# Load_Cell_Biasing.net
KiCad netlist of a schematic drawn in Altium Designer
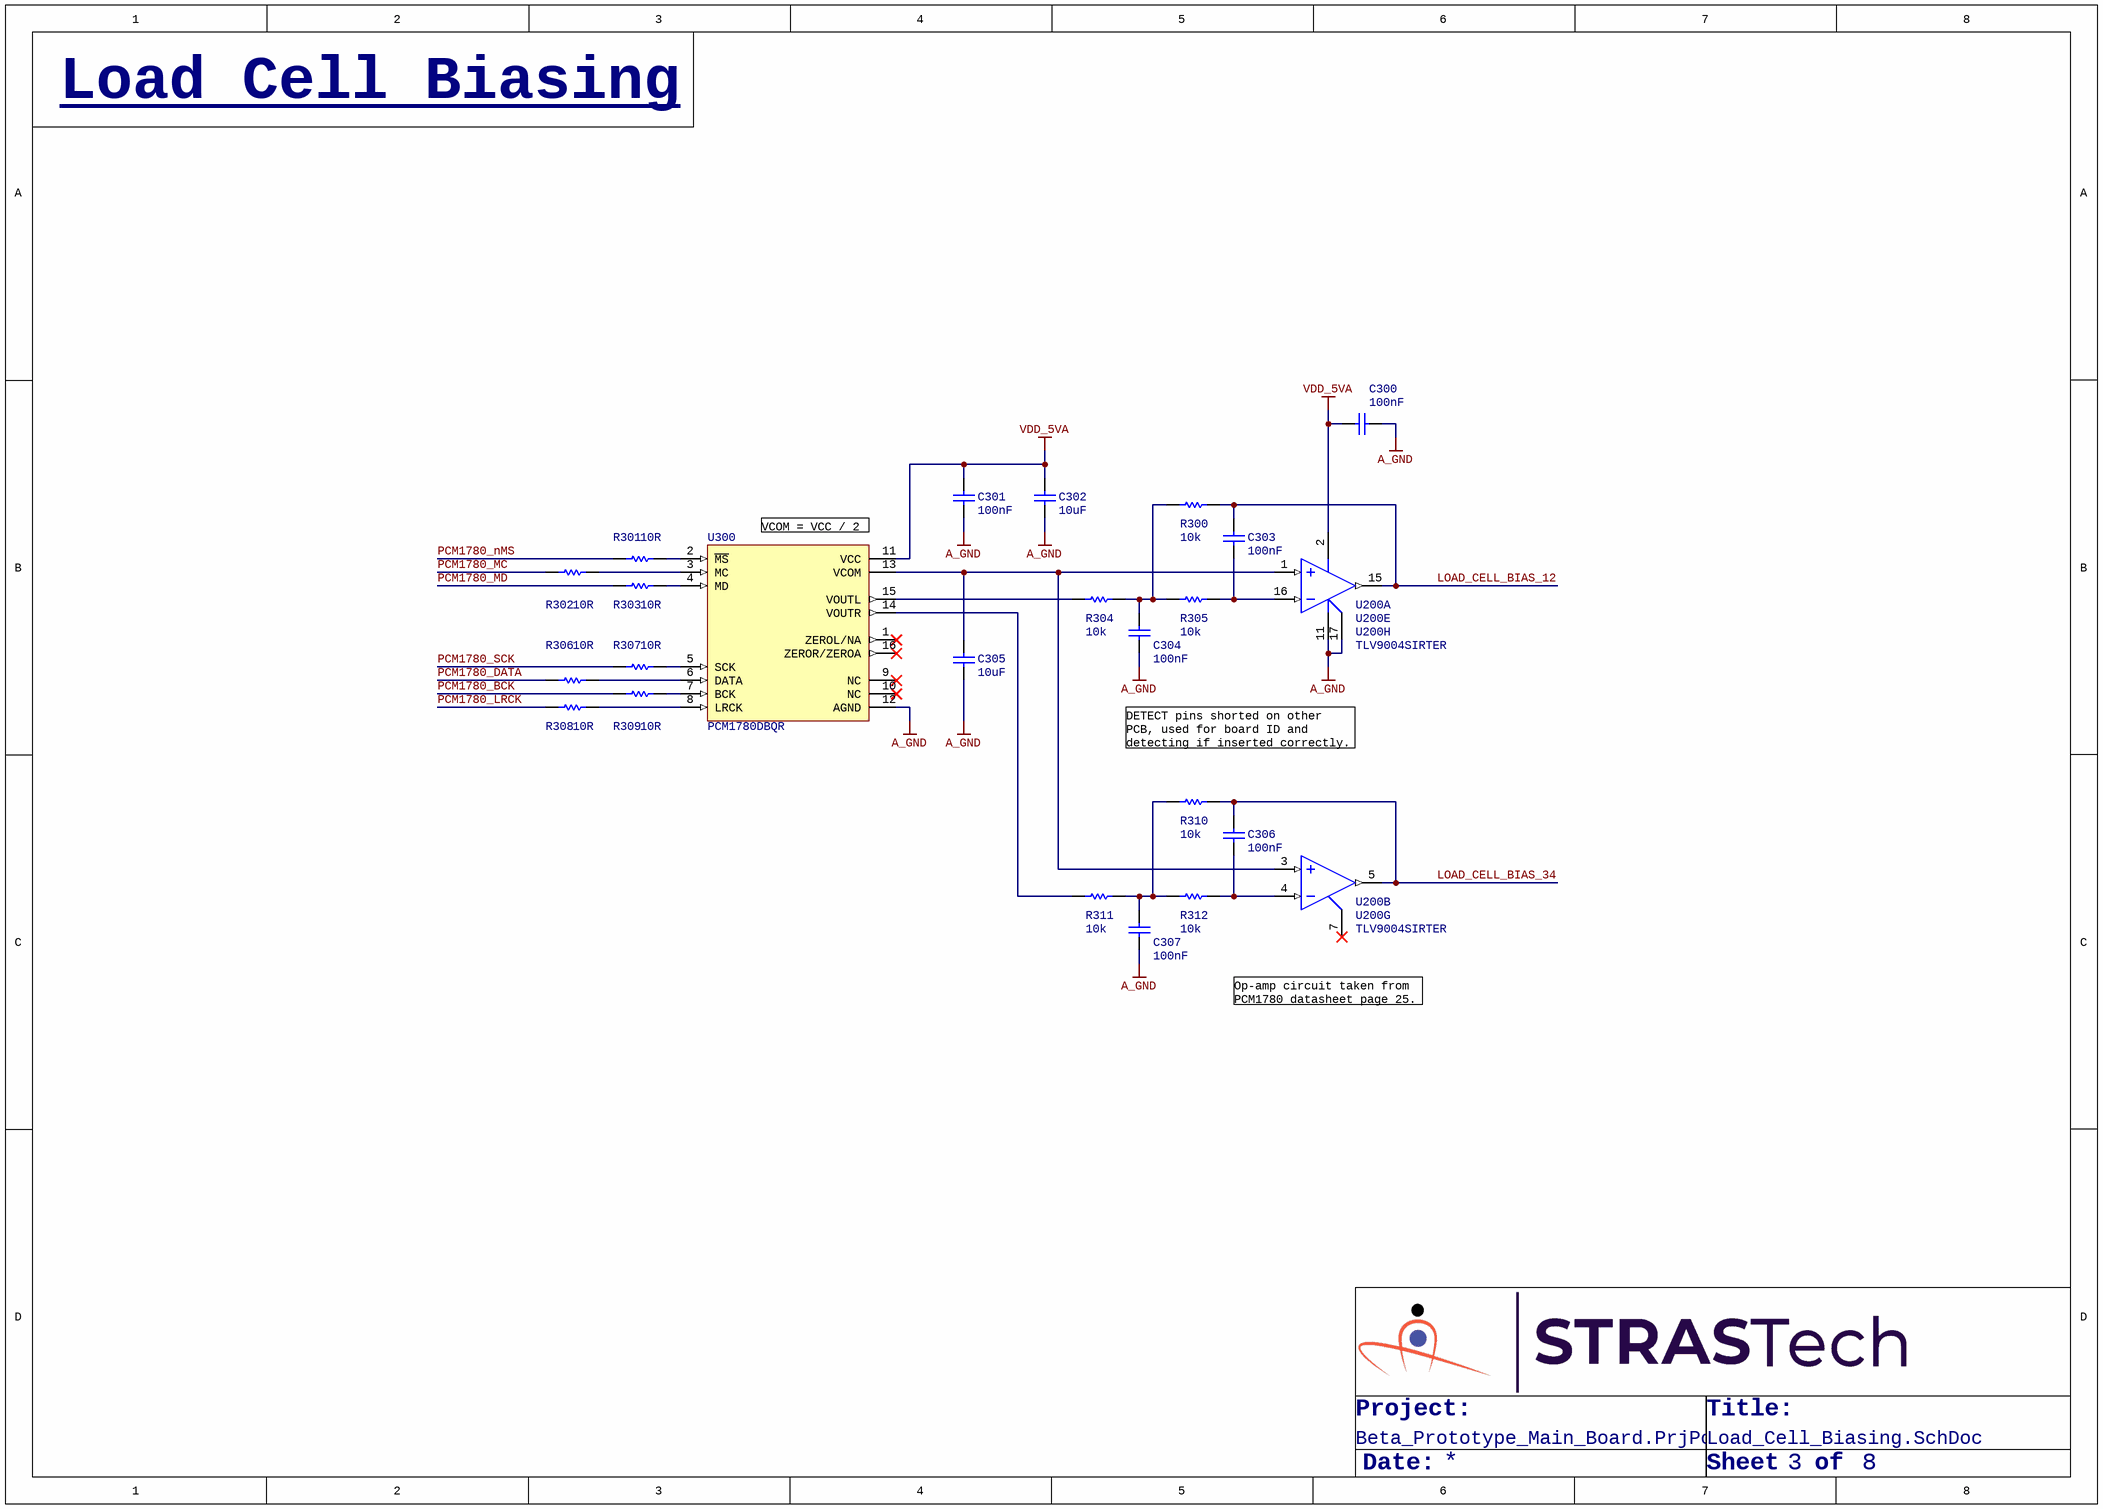
[diagram p0: Load_Cell_Biasing.SchDoc]

(export (version "E")
  (design (tool "Eeschema 10.0.6"))
  (components
    (comp (ref "C300")
      (value "100nF")
      (footprint "Cap,SMD,0402")
      (description "0.1µF ±10% 25V Ceramic Capacitor X7R 0402 (1005 Metric)")
      (fields
        (field (name "VENDOR PART NUMBER") "490-14603-1-ND")
        (field (name "MANUFACTURER") "Murata Electronics")
        (field (name "CREATEDBY") "Judd Foster")
      )
      (libsource (lib "symbols") (part "CAP,Cer,100nF,25VDC,X7R,0402"))
    )
    (comp (ref "C301")
      (value "100nF")
      (footprint "Cap,SMD,0402")
      (description "0.1µF ±10% 25V Ceramic Capacitor X7R 0402 (1005 Metric)")
      (fields
        (field (name "VENDOR PART NUMBER") "490-14603-1-ND")
        (field (name "MANUFACTURER") "Murata Electronics")
        (field (name "CREATEDBY") "Judd Foster")
      )
      (libsource (lib "symbols") (part "CAP,Cer,100nF,25VDC,X7R,0402"))
    )
    (comp (ref "C302")
      (value "10uF")
      (footprint "Cap,SMD,0402")
      (description "10 µF ±20% 10V Ceramic Capacitor X5R 0402 (1005 Metric)")
      (fields
        (field (name "VENDOR PART NUMBER") "1276-1450-1-ND")
        (field (name "MANUFACTURER") "Samsung Electro-Mechanics")
        (field (name "CREATEDBY") "Judd Foster")
      )
      (libsource (lib "symbols") (part "CAP,Cer,10uF,10VDC,X5R,0402"))
    )
    (comp (ref "C303")
      (value "100nF")
      (footprint "Cap,SMD,0402")
      (description "0.1µF ±10% 25V Ceramic Capacitor X7R 0402 (1005 Metric)")
      (fields
        (field (name "VENDOR PART NUMBER") "490-14603-1-ND")
        (field (name "MANUFACTURER") "Murata Electronics")
        (field (name "CREATEDBY") "Judd Foster")
      )
      (libsource (lib "symbols") (part "CAP,Cer,100nF,25VDC,X7R,0402"))
    )
    (comp (ref "C304")
      (value "100nF")
      (footprint "Cap,SMD,0402")
      (description "0.1µF ±10% 25V Ceramic Capacitor X7R 0402 (1005 Metric)")
      (fields
        (field (name "VENDOR PART NUMBER") "490-14603-1-ND")
        (field (name "MANUFACTURER") "Murata Electronics")
        (field (name "CREATEDBY") "Judd Foster")
      )
      (libsource (lib "symbols") (part "CAP,Cer,100nF,25VDC,X7R,0402"))
    )
    (comp (ref "C305")
      (value "10uF")
      (footprint "Cap,SMD,0402")
      (description "10 µF ±20% 10V Ceramic Capacitor X5R 0402 (1005 Metric)")
      (fields
        (field (name "VENDOR PART NUMBER") "1276-1450-1-ND")
        (field (name "MANUFACTURER") "Samsung Electro-Mechanics")
        (field (name "CREATEDBY") "Judd Foster")
      )
      (libsource (lib "symbols") (part "CAP,Cer,10uF,10VDC,X5R,0402"))
    )
    (comp (ref "C306")
      (value "100nF")
      (footprint "Cap,SMD,0402")
      (description "0.1µF ±10% 25V Ceramic Capacitor X7R 0402 (1005 Metric)")
      (fields
        (field (name "VENDOR PART NUMBER") "490-14603-1-ND")
        (field (name "MANUFACTURER") "Murata Electronics")
        (field (name "CREATEDBY") "Judd Foster")
      )
      (libsource (lib "symbols") (part "CAP,Cer,100nF,25VDC,X7R,0402"))
    )
    (comp (ref "C307")
      (value "100nF")
      (footprint "Cap,SMD,0402")
      (description "0.1µF ±10% 25V Ceramic Capacitor X7R 0402 (1005 Metric)")
      (fields
        (field (name "VENDOR PART NUMBER") "490-14603-1-ND")
        (field (name "MANUFACTURER") "Murata Electronics")
        (field (name "CREATEDBY") "Judd Foster")
      )
      (libsource (lib "symbols") (part "CAP,Cer,100nF,25VDC,X7R,0402"))
    )
    (comp (ref "R300")
      (value "10k")
      (footprint "RES,0402")
      (description "10 kOhms ±5% 0.063W, 1/16W Chip Resistor 0402 (1005 Metric) Automotive AEC-Q200 Thick Film")
      (fields
        (field (name "VENDOR PART NUMBER") "RMCF0402JT10K0CT-ND")
        (field (name "MANUFACTURER") "Stackpole Electronics Inc")
        (field (name "CREATEDBY") "Judd Foster")
      )
      (libsource (lib "symbols") (part "RES,10k,5%,0.063W,0402"))
    )
    (comp (ref "R301")
      (value "10R")
      (footprint "RES,0402")
      (description "10 Ohms ±1% 0.063W, 1/16W Chip Resistor 0402 (1005 Metric) Automotive AEC-Q200 Thick Film")
      (fields
        (field (name "MANUFACTURER") "Panasonic Electronic Components")
        (field (name "MANUFACTURER PART NUMBER") "ERJ-2RKF10R0X")
        (field (name "CREATEDBY") "Judd Foster")
      )
      (libsource (lib "symbols") (part "RES,10R,1%,0.063W,0402"))
    )
    (comp (ref "R302")
      (value "10R")
      (footprint "RES,0402")
      (description "10 Ohms ±1% 0.063W, 1/16W Chip Resistor 0402 (1005 Metric) Automotive AEC-Q200 Thick Film")
      (fields
        (field (name "MANUFACTURER") "Panasonic Electronic Components")
        (field (name "MANUFACTURER PART NUMBER") "ERJ-2RKF10R0X")
        (field (name "CREATEDBY") "Judd Foster")
      )
      (libsource (lib "symbols") (part "RES,10R,1%,0.063W,0402"))
    )
    (comp (ref "R303")
      (value "10R")
      (footprint "RES,0402")
      (description "10 Ohms ±1% 0.063W, 1/16W Chip Resistor 0402 (1005 Metric) Automotive AEC-Q200 Thick Film")
      (fields
        (field (name "MANUFACTURER") "Panasonic Electronic Components")
        (field (name "MANUFACTURER PART NUMBER") "ERJ-2RKF10R0X")
        (field (name "CREATEDBY") "Judd Foster")
      )
      (libsource (lib "symbols") (part "RES,10R,1%,0.063W,0402"))
    )
    (comp (ref "R304")
      (value "10k")
      (footprint "RES,0402")
      (description "10 kOhms ±5% 0.063W, 1/16W Chip Resistor 0402 (1005 Metric) Automotive AEC-Q200 Thick Film")
      (fields
        (field (name "VENDOR PART NUMBER") "RMCF0402JT10K0CT-ND")
        (field (name "MANUFACTURER") "Stackpole Electronics Inc")
        (field (name "CREATEDBY") "Judd Foster")
      )
      (libsource (lib "symbols") (part "RES,10k,5%,0.063W,0402"))
    )
    (comp (ref "R305")
      (value "10k")
      (footprint "RES,0402")
      (description "10 kOhms ±5% 0.063W, 1/16W Chip Resistor 0402 (1005 Metric) Automotive AEC-Q200 Thick Film")
      (fields
        (field (name "VENDOR PART NUMBER") "RMCF0402JT10K0CT-ND")
        (field (name "MANUFACTURER") "Stackpole Electronics Inc")
        (field (name "CREATEDBY") "Judd Foster")
      )
      (libsource (lib "symbols") (part "RES,10k,5%,0.063W,0402"))
    )
    (comp (ref "R306")
      (value "10R")
      (footprint "RES,0402")
      (description "10 Ohms ±1% 0.063W, 1/16W Chip Resistor 0402 (1005 Metric) Automotive AEC-Q200 Thick Film")
      (fields
        (field (name "MANUFACTURER") "Panasonic Electronic Components")
        (field (name "MANUFACTURER PART NUMBER") "ERJ-2RKF10R0X")
        (field (name "CREATEDBY") "Judd Foster")
      )
      (libsource (lib "symbols") (part "RES,10R,1%,0.063W,0402"))
    )
    (comp (ref "R307")
      (value "10R")
      (footprint "RES,0402")
      (description "10 Ohms ±1% 0.063W, 1/16W Chip Resistor 0402 (1005 Metric) Automotive AEC-Q200 Thick Film")
      (fields
        (field (name "MANUFACTURER") "Panasonic Electronic Components")
        (field (name "MANUFACTURER PART NUMBER") "ERJ-2RKF10R0X")
        (field (name "CREATEDBY") "Judd Foster")
      )
      (libsource (lib "symbols") (part "RES,10R,1%,0.063W,0402"))
    )
    (comp (ref "R308")
      (value "10R")
      (footprint "RES,0402")
      (description "10 Ohms ±1% 0.063W, 1/16W Chip Resistor 0402 (1005 Metric) Automotive AEC-Q200 Thick Film")
      (fields
        (field (name "MANUFACTURER") "Panasonic Electronic Components")
        (field (name "MANUFACTURER PART NUMBER") "ERJ-2RKF10R0X")
        (field (name "CREATEDBY") "Judd Foster")
      )
      (libsource (lib "symbols") (part "RES,10R,1%,0.063W,0402"))
    )
    (comp (ref "R309")
      (value "10R")
      (footprint "RES,0402")
      (description "10 Ohms ±1% 0.063W, 1/16W Chip Resistor 0402 (1005 Metric) Automotive AEC-Q200 Thick Film")
      (fields
        (field (name "MANUFACTURER") "Panasonic Electronic Components")
        (field (name "MANUFACTURER PART NUMBER") "ERJ-2RKF10R0X")
        (field (name "CREATEDBY") "Judd Foster")
      )
      (libsource (lib "symbols") (part "RES,10R,1%,0.063W,0402"))
    )
    (comp (ref "R310")
      (value "10k")
      (footprint "RES,0402")
      (description "10 kOhms ±5% 0.063W, 1/16W Chip Resistor 0402 (1005 Metric) Automotive AEC-Q200 Thick Film")
      (fields
        (field (name "VENDOR PART NUMBER") "RMCF0402JT10K0CT-ND")
        (field (name "MANUFACTURER") "Stackpole Electronics Inc")
        (field (name "CREATEDBY") "Judd Foster")
      )
      (libsource (lib "symbols") (part "RES,10k,5%,0.063W,0402"))
    )
    (comp (ref "R311")
      (value "10k")
      (footprint "RES,0402")
      (description "10 kOhms ±5% 0.063W, 1/16W Chip Resistor 0402 (1005 Metric) Automotive AEC-Q200 Thick Film")
      (fields
        (field (name "VENDOR PART NUMBER") "RMCF0402JT10K0CT-ND")
        (field (name "MANUFACTURER") "Stackpole Electronics Inc")
        (field (name "CREATEDBY") "Judd Foster")
      )
      (libsource (lib "symbols") (part "RES,10k,5%,0.063W,0402"))
    )
    (comp (ref "R312")
      (value "10k")
      (footprint "RES,0402")
      (description "10 kOhms ±5% 0.063W, 1/16W Chip Resistor 0402 (1005 Metric) Automotive AEC-Q200 Thick Film")
      (fields
        (field (name "VENDOR PART NUMBER") "RMCF0402JT10K0CT-ND")
        (field (name "MANUFACTURER") "Stackpole Electronics Inc")
        (field (name "CREATEDBY") "Judd Foster")
      )
      (libsource (lib "symbols") (part "RES,10k,5%,0.063W,0402"))
    )
    (comp (ref "U200")
      (value "TLV9004SIRTER")
      (footprint "IC,QFN-16,3x3")
      (description "General Purpose Amplifier 4 Circuit Rail-to-Rail 16-WQFN (3x3)")
      (fields
        (field (name "MANUFACTURER") "Texas Instruments")
        (field (name "VENDOR PART NUMBER") "296-51829-1-ND")
        (field (name "CREATEDBY") "Judd Foster")
      )
      (libsource (lib "symbols") (part "TLV9004SIRTER"))
    )
    (comp (ref "U300")
      (value "PCM1780DBQR")
      (footprint "IC,TSSOP-16,W3.9,P0.635MM")
      (description "DAC, Audio 24 b 200k I²S 16-SSOP")
      (fields
        (field (name "MANUFACTURER") "Texas Instruments")
        (field (name "VENDOR PART NUMBER") "296-41373-1-ND")
        (field (name "CREATEDBY") "Judd Foster")
      )
      (libsource (lib "symbols") (part "PCM1780DBQR"))
    )
  )
  (nets
    (net (code "1") (name "/LOAD_CELL_BIAS_12") (class "Default")
      (node (ref "C303") (pin "2") (pinfunction "2_2") (pintype "passive"))
      (node (ref "R300") (pin "1") (pinfunction "1_1") (pintype "passive"))
      (node (ref "U200") (pin "15") (pinfunction "OUT1_15") (pintype "output"))
    )
    (net (code "2") (name "/LOAD_CELL_BIAS_34") (class "Default")
      (node (ref "C306") (pin "2") (pinfunction "2_2") (pintype "passive"))
      (node (ref "R310") (pin "1") (pinfunction "1_1") (pintype "passive"))
      (node (ref "U200") (pin "5") (pinfunction "OUT2_5") (pintype "output"))
    )
    (net (code "3") (name "/PCM1780_BCK") (class "Default")
      (node (ref "R309") (pin "1") (pinfunction "1_1") (pintype "passive"))
    )
    (net (code "4") (name "/PCM1780_DATA") (class "Default")
      (node (ref "R306") (pin "1") (pinfunction "1_1") (pintype "passive"))
    )
    (net (code "5") (name "/PCM1780_LRCK") (class "Default")
      (node (ref "R308") (pin "1") (pinfunction "1_1") (pintype "passive"))
    )
    (net (code "6") (name "/PCM1780_MC") (class "Default")
      (node (ref "R302") (pin "1") (pinfunction "1_1") (pintype "passive"))
    )
    (net (code "7") (name "/PCM1780_MD") (class "Default")
      (node (ref "R303") (pin "1") (pinfunction "1_1") (pintype "passive"))
    )
    (net (code "8") (name "/PCM1780_SCK") (class "Default")
      (node (ref "R307") (pin "1") (pinfunction "1_1") (pintype "passive"))
    )
    (net (code "9") (name "/PCM1780_nMS") (class "Default")
      (node (ref "R301") (pin "1") (pinfunction "1_1") (pintype "passive"))
    )
    (net (code "10") (name "A_GND") (class "Default")
      (node (ref "C300") (pin "1") (pinfunction "1_1") (pintype "passive"))
      (node (ref "C301") (pin "1") (pinfunction "1_1") (pintype "passive"))
      (node (ref "C302") (pin "1") (pinfunction "1_1") (pintype "passive"))
      (node (ref "C304") (pin "1") (pinfunction "1_1") (pintype "passive"))
      (node (ref "C305") (pin "2") (pinfunction "2_2") (pintype "passive"))
      (node (ref "C307") (pin "1") (pinfunction "1_1") (pintype "passive"))
      (node (ref "U200") (pin "11") (pinfunction "V-_11") (pintype "power_in"))
      (node (ref "U200") (pin "17") (pinfunction "PAD_17") (pintype "power_in"))
      (node (ref "U300") (pin "12") (pinfunction "AGND_12") (pintype "power_in"))
    )
    (net (code "11") (name "Net-(C304-Pad2)") (class "Default")
      (node (ref "C304") (pin "2") (pinfunction "2_2") (pintype "passive"))
      (node (ref "R300") (pin "2") (pinfunction "2_2") (pintype "passive"))
      (node (ref "R304") (pin "2") (pinfunction "2_2") (pintype "passive"))
      (node (ref "R305") (pin "1") (pinfunction "1_1") (pintype "passive"))
    )
    (net (code "12") (name "Net-(C307-Pad2)") (class "Default")
      (node (ref "C307") (pin "2") (pinfunction "2_2") (pintype "passive"))
      (node (ref "R310") (pin "2") (pinfunction "2_2") (pintype "passive"))
      (node (ref "R311") (pin "2") (pinfunction "2_2") (pintype "passive"))
      (node (ref "R312") (pin "1") (pinfunction "1_1") (pintype "passive"))
    )
    (net (code "13") (name "Net-(U200A-IN1+)") (class "Default")
      (node (ref "C305") (pin "1") (pinfunction "1_1") (pintype "passive"))
      (node (ref "U200") (pin "1") (pinfunction "IN1+_1") (pintype "input"))
      (node (ref "U200") (pin "3") (pinfunction "IN2+_3") (pintype "input"))
      (node (ref "U300") (pin "13") (pinfunction "VCOM_13") (pintype "power_in"))
    )
    (net (code "14") (name "Net-(U200A-IN1-)") (class "Default")
      (node (ref "C303") (pin "1") (pinfunction "1_1") (pintype "passive"))
      (node (ref "R305") (pin "2") (pinfunction "2_2") (pintype "passive"))
      (node (ref "U200") (pin "16") (pinfunction "IN1-_16") (pintype "input"))
    )
    (net (code "15") (name "Net-(U200B-IN2-)") (class "Default")
      (node (ref "C306") (pin "1") (pinfunction "1_1") (pintype "passive"))
      (node (ref "R312") (pin "2") (pinfunction "2_2") (pintype "passive"))
      (node (ref "U200") (pin "4") (pinfunction "IN2-_4") (pintype "input"))
    )
    (net (code "16") (name "Net-(U300-BCK)") (class "Default")
      (node (ref "R309") (pin "2") (pinfunction "2_2") (pintype "passive"))
      (node (ref "U300") (pin "7") (pinfunction "BCK_7") (pintype "input"))
    )
    (net (code "17") (name "Net-(U300-DATA)") (class "Default")
      (node (ref "R306") (pin "2") (pinfunction "2_2") (pintype "passive"))
      (node (ref "U300") (pin "6") (pinfunction "DATA_6") (pintype "input"))
    )
    (net (code "18") (name "Net-(U300-LRCK)") (class "Default")
      (node (ref "R308") (pin "2") (pinfunction "2_2") (pintype "passive"))
      (node (ref "U300") (pin "8") (pinfunction "LRCK_8") (pintype "input"))
    )
    (net (code "19") (name "Net-(U300-MC)") (class "Default")
      (node (ref "R302") (pin "2") (pinfunction "2_2") (pintype "passive"))
      (node (ref "U300") (pin "3") (pinfunction "MC_3") (pintype "input"))
    )
    (net (code "20") (name "Net-(U300-MD)") (class "Default")
      (node (ref "R303") (pin "2") (pinfunction "2_2") (pintype "passive"))
      (node (ref "U300") (pin "4") (pinfunction "MD_4") (pintype "input"))
    )
    (net (code "21") (name "Net-(U300-SCK)") (class "Default")
      (node (ref "R307") (pin "2") (pinfunction "2_2") (pintype "passive"))
      (node (ref "U300") (pin "5") (pinfunction "SCK_5") (pintype "input"))
    )
    (net (code "22") (name "Net-(U300-VOUTL)") (class "Default")
      (node (ref "R304") (pin "1") (pinfunction "1_1") (pintype "passive"))
      (node (ref "U300") (pin "15") (pinfunction "VOUTL_15") (pintype "output"))
    )
    (net (code "23") (name "Net-(U300-VOUTR)") (class "Default")
      (node (ref "R311") (pin "1") (pinfunction "1_1") (pintype "passive"))
      (node (ref "U300") (pin "14") (pinfunction "VOUTR_14") (pintype "output"))
    )
    (net (code "24") (name "Net-(U300-~{MS})") (class "Default")
      (node (ref "R301") (pin "2") (pinfunction "2_2") (pintype "passive"))
      (node (ref "U300") (pin "2") (pinfunction "~{MS}_2") (pintype "input"))
    )
    (net (code "25") (name "VDD_5VA") (class "Default")
      (node (ref "C300") (pin "2") (pinfunction "2_2") (pintype "passive"))
      (node (ref "C301") (pin "2") (pinfunction "2_2") (pintype "passive"))
      (node (ref "C302") (pin "2") (pinfunction "2_2") (pintype "passive"))
      (node (ref "U200") (pin "2") (pinfunction "V+_2") (pintype "power_in"))
      (node (ref "U300") (pin "11") (pinfunction "VCC_11") (pintype "power_in"))
    )
    (net (code "26") (name "unconnected-(U200G-~{SHDN}34-Pad7)") (class "Default")
      (node (ref "U200") (pin "7") (pinfunction "~{SHDN}34_7") (pintype "power_in+no_connect"))
    )
    (net (code "27") (name "unconnected-(U300-NC-Pad9)") (class "Default")
      (node (ref "U300") (pin "9") (pinfunction "NC_9") (pintype "passive+no_connect"))
    )
    (net (code "28") (name "unconnected-(U300-NC-Pad10)") (class "Default")
      (node (ref "U300") (pin "10") (pinfunction "NC_10") (pintype "passive+no_connect"))
    )
    (net (code "29") (name "unconnected-(U300-ZEROL{slash}NA-Pad1)") (class "Default")
      (node (ref "U300") (pin "1") (pinfunction "ZEROL/NA_1") (pintype "output+no_connect"))
    )
    (net (code "30") (name "unconnected-(U300-ZEROR{slash}ZEROA-Pad16)") (class "Default")
      (node (ref "U300") (pin "16") (pinfunction "ZEROR/ZEROA_16") (pintype "output+no_connect"))
    )
  )
)
